# Mando_v0.net
KiCad netlist of a schematic drawn in Altium Designer
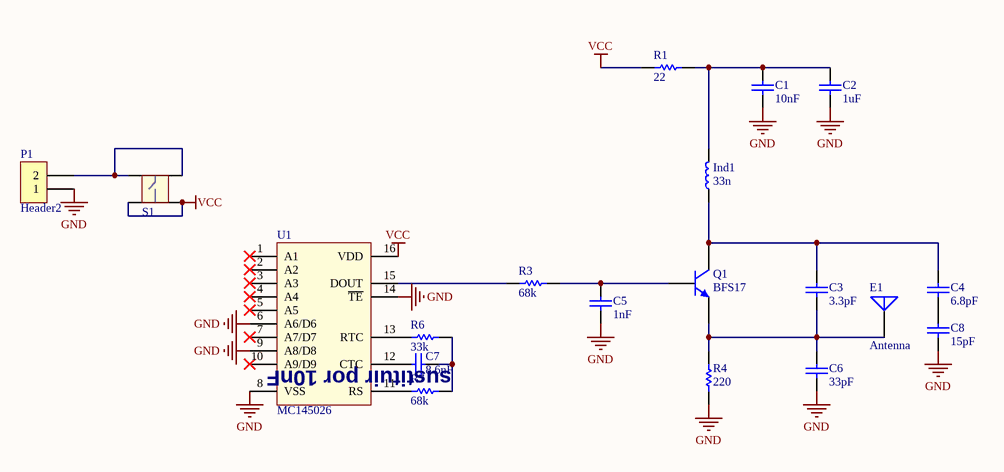
[diagram p0: Mando_v0.SchDoc]

(export (version "E")
  (design (tool "Eeschema 10.0.6"))
  (components
    (comp (ref "C1")
      (value "10nF")
      (footprint "0805_CAP")
      (fields (field (name "Comment") "Capacitor"))
      (libsource (lib "epf") (part "Cap"))
    )
    (comp (ref "C2")
      (value "1uF")
      (footprint "0805_CAP")
      (fields (field (name "Comment") "Capacitor"))
      (libsource (lib "epf") (part "Cap"))
    )
    (comp (ref "C3")
      (value "3.3pF")
      (footprint "0805_CAP")
      (fields (field (name "Comment") "Capacitor"))
      (libsource (lib "epf") (part "Cap"))
    )
    (comp (ref "C4")
      (value "6.8pF")
      (footprint "0805_CAP")
      (fields (field (name "Comment") "Capacitor"))
      (libsource (lib "epf") (part "Cap"))
    )
    (comp (ref "C5")
      (value "1nF")
      (footprint "0805_CAP")
      (fields (field (name "Comment") "Capacitor"))
      (libsource (lib "epf") (part "Cap"))
    )
    (comp (ref "C6")
      (value "33pF")
      (footprint "0805_CAP")
      (fields (field (name "Comment") "Capacitor"))
      (libsource (lib "epf") (part "Cap"))
    )
    (comp (ref "C7")
      (value "8.6nF")
      (footprint "CAP0805")
      (fields (field (name "Comment") "Capacitor"))
      (libsource (lib "epf") (part "Cap"))
    )
    (comp (ref "C8")
      (value "15pF")
      (footprint "CAP0805")
      (fields (field (name "Comment") "Capacitor"))
      (libsource (lib "epf") (part "Cap"))
    )
    (comp (ref "E1")
      (value "Antenna")
      (footprint "PIN1")
      (description "Generic Antenna")
      (fields (field (name "PUBLISHER") "Altium Limited"))
      (libsource (lib "Miscellaneous Devices") (part "Antenna"))
    )
    (comp (ref "Ind1")
      (value "Ind2")
      (footprint "IND0603")
      (fields (field (name "VALOR") "33n"))
      (libsource (lib "epf") (part "Ind2"))
    )
    (comp (ref "P1") (value "Header2") (footprint "HeaderHx2") (libsource (lib "epf") (part "Header2")))
    (comp (ref "Q1")
      (value "BFS17")
      (footprint "SOT23")
      (description "NPN 1 GHz Wideband Transistor")
      (fields (field (name "PUBLISHER") "Altium Limited"))
      (libsource (lib "epf") (part "BFS17"))
    )
    (comp (ref "R1")
      (value "22")
      (footprint "0805_RES")
      (fields (field (name "Comment") "Resistor"))
      (libsource (lib "epf") (part "Res"))
    )
    (comp (ref "R3")
      (value "68k")
      (footprint "0805_RES")
      (fields (field (name "Comment") "Resistor"))
      (libsource (lib "epf") (part "Res"))
    )
    (comp (ref "R4")
      (value "220")
      (footprint "0805_RES")
      (fields (field (name "Comment") "Resistor"))
      (libsource (lib "epf") (part "Res"))
    )
    (comp (ref "R6")
      (value "33k")
      (footprint "RES0805")
      (fields (field (name "Comment") "Resistor"))
      (libsource (lib "epf") (part "Res"))
    )
    (comp (ref "R7")
      (value "68k")
      (footprint "RES0805")
      (fields (field (name "Comment") "Resistor"))
      (libsource (lib "epf") (part "Res"))
    )
    (comp (ref "S1") (value "Pulsador") (footprint "SW-PB6mm") (libsource (lib "epf") (part "Pulsador")))
    (comp (ref "U1")
      (value "MC145026")
      (footprint "SOIC127P602-16BN")
      (description "ENCODER")
      (libsource (lib "epf") (part "MC145026"))
    )
  )
  (nets
    (net (code "1") (name "GND") (class "Default")
      (node (ref "C1") (pin "1") (pinfunction "1_1") (pintype "passive"))
      (node (ref "C2") (pin "1") (pinfunction "1_1") (pintype "passive"))
      (node (ref "C5") (pin "1") (pinfunction "1_1") (pintype "passive"))
      (node (ref "C6") (pin "1") (pinfunction "1_1") (pintype "passive"))
      (node (ref "C8") (pin "1") (pinfunction "1_1") (pintype "passive"))
      (node (ref "P1") (pin "1") (pinfunction "1_1") (pintype "passive"))
      (node (ref "R4") (pin "2") (pinfunction "2_2") (pintype "passive"))
      (node (ref "U1") (pin "14") (pinfunction "TE_14") (pintype "passive"))
      (node (ref "U1") (pin "6") (pinfunction "A6/D6_6") (pintype "passive"))
      (node (ref "U1") (pin "8") (pinfunction "VSS_8") (pintype "passive"))
      (node (ref "U1") (pin "9") (pinfunction "A8/D8_9") (pintype "passive"))
    )
    (net (code "2") (name "Net-(C1-Pad2)") (class "Default")
      (node (ref "C1") (pin "2") (pinfunction "2_2") (pintype "passive"))
      (node (ref "C2") (pin "2") (pinfunction "2_2") (pintype "passive"))
      (node (ref "Ind1") (pin "2") (pinfunction "2_2") (pintype "passive"))
      (node (ref "R1") (pin "2") (pinfunction "2_2") (pintype "passive"))
    )
    (net (code "3") (name "Net-(C4-Pad1)") (class "Default")
      (node (ref "C4") (pin "1") (pinfunction "1_1") (pintype "passive"))
      (node (ref "C8") (pin "2") (pinfunction "2_2") (pintype "passive"))
    )
    (net (code "4") (name "Net-(C7-Pad1)") (class "Default")
      (node (ref "C7") (pin "1") (pinfunction "1_1") (pintype "passive"))
      (node (ref "R6") (pin "2") (pinfunction "2_2") (pintype "passive"))
      (node (ref "R7") (pin "2") (pinfunction "2_2") (pintype "passive"))
    )
    (net (code "5") (name "Net-(E1-A)") (class "Default")
      (node (ref "C3") (pin "1") (pinfunction "1_1") (pintype "passive"))
      (node (ref "C6") (pin "2") (pinfunction "2_2") (pintype "passive"))
      (node (ref "E1") (pin "1") (pinfunction "A_1") (pintype "passive"))
      (node (ref "Q1") (pin "2") (pinfunction "E_2") (pintype "passive"))
      (node (ref "R4") (pin "1") (pinfunction "1_1") (pintype "passive"))
    )
    (net (code "6") (name "Net-(P1-Pad2)") (class "Default")
      (node (ref "P1") (pin "2") (pinfunction "2_2") (pintype "passive"))
      (node (ref "S1") (pin "1") (pinfunction "1_1") (pintype "passive"))
      (node (ref "S1") (pin "2") (pinfunction "2_2") (pintype "passive"))
    )
    (net (code "7") (name "Net-(Q1-B)") (class "Default")
      (node (ref "C5") (pin "2") (pinfunction "2_2") (pintype "passive"))
      (node (ref "Q1") (pin "1") (pinfunction "B_1") (pintype "passive"))
      (node (ref "R3") (pin "2") (pinfunction "2_2") (pintype "passive"))
    )
    (net (code "8") (name "Net-(Q1-C)") (class "Default")
      (node (ref "C3") (pin "2") (pinfunction "2_2") (pintype "passive"))
      (node (ref "C4") (pin "2") (pinfunction "2_2") (pintype "passive"))
      (node (ref "Ind1") (pin "1") (pinfunction "1_1") (pintype "passive"))
      (node (ref "Q1") (pin "3") (pinfunction "C_3") (pintype "passive"))
    )
    (net (code "9") (name "Net-(U1-CTC)") (class "Default")
      (node (ref "C7") (pin "2") (pinfunction "2_2") (pintype "passive"))
      (node (ref "U1") (pin "12") (pinfunction "CTC_12") (pintype "passive"))
    )
    (net (code "10") (name "Net-(U1-DOUT)") (class "Default")
      (node (ref "R3") (pin "1") (pinfunction "1_1") (pintype "passive"))
      (node (ref "U1") (pin "15") (pinfunction "DOUT_15") (pintype "passive"))
    )
    (net (code "11") (name "Net-(U1-RS)") (class "Default")
      (node (ref "R7") (pin "1") (pinfunction "1_1") (pintype "passive"))
      (node (ref "U1") (pin "11") (pinfunction "RS_11") (pintype "passive"))
    )
    (net (code "12") (name "Net-(U1-RTC)") (class "Default")
      (node (ref "R6") (pin "1") (pinfunction "1_1") (pintype "passive"))
      (node (ref "U1") (pin "13") (pinfunction "RTC_13") (pintype "passive"))
    )
    (net (code "13") (name "VCC") (class "Default")
      (node (ref "R1") (pin "1") (pinfunction "1_1") (pintype "passive"))
      (node (ref "S1") (pin "3") (pinfunction "3_3") (pintype "passive"))
      (node (ref "S1") (pin "4") (pinfunction "4_4") (pintype "passive"))
      (node (ref "U1") (pin "16") (pinfunction "VDD_16") (pintype "passive"))
    )
    (net (code "14") (name "unconnected-(U1-A1-Pad1)") (class "Default")
      (node (ref "U1") (pin "1") (pinfunction "A1_1") (pintype "passive+no_connect"))
    )
    (net (code "15") (name "unconnected-(U1-A2-Pad2)") (class "Default")
      (node (ref "U1") (pin "2") (pinfunction "A2_2") (pintype "passive+no_connect"))
    )
    (net (code "16") (name "unconnected-(U1-A3-Pad3)") (class "Default")
      (node (ref "U1") (pin "3") (pinfunction "A3_3") (pintype "passive+no_connect"))
    )
    (net (code "17") (name "unconnected-(U1-A4-Pad4)") (class "Default")
      (node (ref "U1") (pin "4") (pinfunction "A4_4") (pintype "passive+no_connect"))
    )
    (net (code "18") (name "unconnected-(U1-A5-Pad5)") (class "Default")
      (node (ref "U1") (pin "5") (pinfunction "A5_5") (pintype "passive+no_connect"))
    )
    (net (code "19") (name "unconnected-(U1-A7{slash}D7-Pad7)") (class "Default")
      (node (ref "U1") (pin "7") (pinfunction "A7/D7_7") (pintype "passive+no_connect"))
    )
    (net (code "20") (name "unconnected-(U1-A9{slash}D9-Pad10)") (class "Default")
      (node (ref "U1") (pin "10") (pinfunction "A9/D9_10") (pintype "passive+no_connect"))
    )
  )
)
